# Filtre_passe-bande_5k.net
KiCad netlist of a schematic drawn in Altium Designer
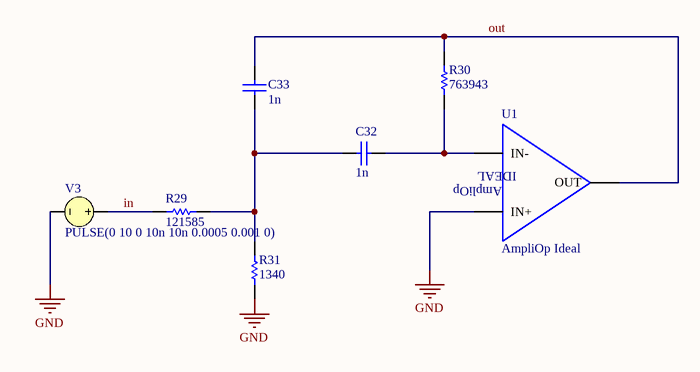
[diagram p0: Filtre passe-bande 5k.SchDoc]

(export (version "E")
  (design (tool "Eeschema 10.0.6"))
  (components
    (comp (ref "C32")
      (value "1n")
      (description "Capacitor")
      (libsource (lib "Simulation Generic Components") (part "Capacitor"))
    )
    (comp (ref "C33")
      (value "1n")
      (description "Capacitor")
      (libsource (lib "Simulation Generic Components") (part "Capacitor"))
    )
    (comp (ref "R29")
      (value "121585")
      (description "Resistor")
      (libsource (lib "Simulation Generic Components") (part "Resistor"))
    )
    (comp (ref "R30")
      (value "763943")
      (description "Resistor")
      (libsource (lib "Simulation Generic Components") (part "Resistor"))
    )
    (comp (ref "R31")
      (value "1340")
      (description "Resistor")
      (libsource (lib "Simulation Generic Components") (part "Resistor"))
    )
    (comp (ref "U1") (value "AmpliOp Ideal") (libsource (lib "Librarie_S2") (part "AmpliOp_ideal")))
    (comp (ref "V3")
      (value "PULSE(0 10 0 10n 10n 0.0005 0.001 0)")
      (description "Voltage Source")
      (fields (field (name "PUBLISHER") "Altium Limited"))
      (libsource (lib "Simulation Generic Components") (part "VSRC"))
    )
  )
  (nets
    (net (code "1") (name "/in") (class "Default")
      (node (ref "R29") (pin "2") (pinfunction "2_2") (pintype "passive"))
      (node (ref "V3") (pin "1") (pinfunction "1_1") (pintype "passive"))
    )
    (net (code "2") (name "/out") (class "Default")
      (node (ref "C33") (pin "2") (pinfunction "2_2") (pintype "passive"))
      (node (ref "R30") (pin "2") (pinfunction "2_2") (pintype "passive"))
      (node (ref "U1") (pin "3") (pinfunction "OUT_3") (pintype "passive"))
    )
    (net (code "3") (name "GND") (class "Default")
      (node (ref "R31") (pin "2") (pinfunction "2_2") (pintype "passive"))
      (node (ref "U1") (pin "1") (pinfunction "IN+_1") (pintype "passive"))
      (node (ref "V3") (pin "2") (pinfunction "2_2") (pintype "passive"))
    )
    (net (code "4") (name "Net-(C32-Pad1)") (class "Default")
      (node (ref "C32") (pin "1") (pinfunction "1_1") (pintype "passive"))
      (node (ref "C33") (pin "1") (pinfunction "1_1") (pintype "passive"))
      (node (ref "R29") (pin "1") (pinfunction "1_1") (pintype "passive"))
      (node (ref "R31") (pin "1") (pinfunction "1_1") (pintype "passive"))
    )
    (net (code "5") (name "Net-(U1-IN-)") (class "Default")
      (node (ref "C32") (pin "2") (pinfunction "2_2") (pintype "passive"))
      (node (ref "R30") (pin "1") (pinfunction "1_1") (pintype "passive"))
      (node (ref "U1") (pin "2") (pinfunction "IN-_2") (pintype "passive"))
    )
  )
)
